# Sheet5.net
KiCad netlist of a schematic drawn in Altium Designer
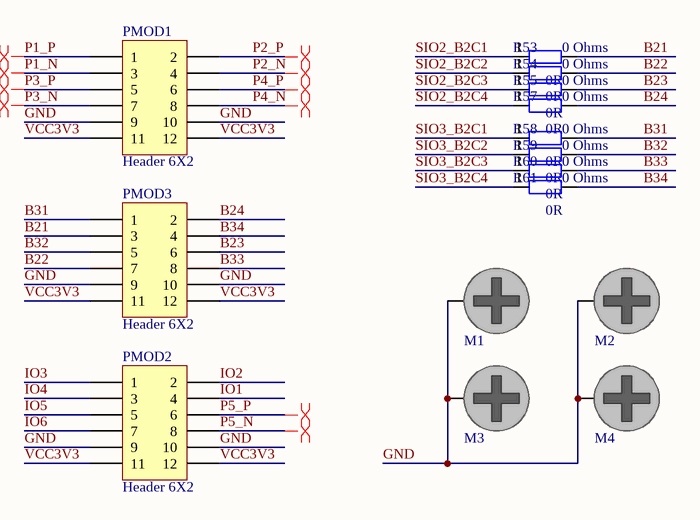
[diagram p0: Sheet5.SchDoc]

(export (version "E")
  (design (tool "Eeschema 10.0.6"))
  (components
    (comp (ref "M1")
      (value "DNP/MH")
      (footprint "SCMH_M2")
      (description "SCREW mouting, M2, 2.0mm diameter and 4.0mm PanHead")
      (libsource (lib "Mechanical") (part "SCMH_M2"))
    )
    (comp (ref "M2")
      (value "DNP/MH")
      (footprint "SCMH_M2")
      (description "SCREW mouting, M2, 2.0mm diameter and 4.0mm PanHead")
      (libsource (lib "Mechanical") (part "SCMH_M2"))
    )
    (comp (ref "M3")
      (value "DNP/MH")
      (footprint "SCMH_M2")
      (description "SCREW mouting, M2, 2.0mm diameter and 4.0mm PanHead")
      (libsource (lib "Mechanical") (part "SCMH_M2"))
    )
    (comp (ref "M4")
      (value "DNP/MH")
      (footprint "SCMH_M2")
      (description "SCREW mouting, M2, 2.0mm diameter and 4.0mm PanHead")
      (libsource (lib "Mechanical") (part "SCMH_M2"))
    )
    (comp (ref "PMOD1")
      (value "Header 6X2")
      (footprint "HDR2X6")
      (description "Header, 6-Pin, Dual row")
      (fields (field (name "PUBLISHER") "Altium Limited"))
      (libsource (lib "Miscellaneous Connectors") (part "Header 6X2"))
    )
    (comp (ref "PMOD2")
      (value "Header 6X2")
      (footprint "HDR2X6")
      (description "Header, 6-Pin, Dual row")
      (fields (field (name "PUBLISHER") "Altium Limited"))
      (libsource (lib "Miscellaneous Connectors") (part "Header 6X2"))
    )
    (comp (ref "PMOD3")
      (value "Header 6X2")
      (footprint "HDR2X6")
      (description "Header, 6-Pin, Dual row")
      (fields (field (name "PUBLISHER") "Altium Limited"))
      (libsource (lib "Miscellaneous Connectors") (part "Header 6X2"))
    )
    (comp (ref "R53")
      (value "0 Ohms")
      (footprint "RES0402i")
      (description "0402, 0R")
      (fields
        (field (name "PART NUMBER") "CRCW04020000Z0EDC")
        (field (name "VOLTAGE") "50V")
        (field (name "ALTIUM_VALUE") "0R")
      )
      (libsource (lib "AmpherLib") (part "Res_0R_0402"))
    )
    (comp (ref "R54")
      (value "0 Ohms")
      (footprint "RES0402i")
      (description "0402, 0R")
      (fields
        (field (name "PART NUMBER") "CRCW04020000Z0EDC")
        (field (name "VOLTAGE") "50V")
        (field (name "ALTIUM_VALUE") "0R")
      )
      (libsource (lib "AmpherLib") (part "Res_0R_0402"))
    )
    (comp (ref "R55")
      (value "0 Ohms")
      (footprint "RES0402i")
      (description "0402, 0R")
      (fields
        (field (name "PART NUMBER") "CRCW04020000Z0EDC")
        (field (name "VOLTAGE") "50V")
        (field (name "ALTIUM_VALUE") "0R")
      )
      (libsource (lib "AmpherLib") (part "Res_0R_0402"))
    )
    (comp (ref "R57")
      (value "0 Ohms")
      (footprint "RES0402i")
      (description "0402, 0R")
      (fields
        (field (name "PART NUMBER") "CRCW04020000Z0EDC")
        (field (name "VOLTAGE") "50V")
        (field (name "ALTIUM_VALUE") "0R")
      )
      (libsource (lib "AmpherLib") (part "Res_0R_0402"))
    )
    (comp (ref "R58")
      (value "0 Ohms")
      (footprint "RES0402i")
      (description "0402, 0R")
      (fields
        (field (name "PART NUMBER") "CRCW04020000Z0EDC")
        (field (name "VOLTAGE") "50V")
        (field (name "ALTIUM_VALUE") "0R")
      )
      (libsource (lib "AmpherLib") (part "Res_0R_0402"))
    )
    (comp (ref "R59")
      (value "0 Ohms")
      (footprint "RES0402i")
      (description "0402, 0R")
      (fields
        (field (name "PART NUMBER") "CRCW04020000Z0EDC")
        (field (name "VOLTAGE") "50V")
        (field (name "ALTIUM_VALUE") "0R")
      )
      (libsource (lib "AmpherLib") (part "Res_0R_0402"))
    )
    (comp (ref "R60")
      (value "0 Ohms")
      (footprint "RES0402i")
      (description "0402, 0R")
      (fields
        (field (name "PART NUMBER") "CRCW04020000Z0EDC")
        (field (name "VOLTAGE") "50V")
        (field (name "ALTIUM_VALUE") "0R")
      )
      (libsource (lib "AmpherLib") (part "Res_0R_0402"))
    )
    (comp (ref "R61")
      (value "0 Ohms")
      (footprint "RES0402i")
      (description "0402, 0R")
      (fields
        (field (name "PART NUMBER") "CRCW04020000Z0EDC")
        (field (name "VOLTAGE") "50V")
        (field (name "ALTIUM_VALUE") "0R")
      )
      (libsource (lib "AmpherLib") (part "Res_0R_0402"))
    )
  )
  (nets
    (net (code "1") (name "/B21") (class "Default")
      (node (ref "PMOD3") (pin "3") (pinfunction "3_3") (pintype "passive"))
      (node (ref "R53") (pin "2") (pinfunction "2_2") (pintype "passive"))
    )
    (net (code "2") (name "/B22") (class "Default")
      (node (ref "PMOD3") (pin "7") (pinfunction "7_7") (pintype "passive"))
      (node (ref "R54") (pin "2") (pinfunction "2_2") (pintype "passive"))
    )
    (net (code "3") (name "/B23") (class "Default")
      (node (ref "PMOD3") (pin "6") (pinfunction "6_6") (pintype "passive"))
      (node (ref "R55") (pin "2") (pinfunction "2_2") (pintype "passive"))
    )
    (net (code "4") (name "/B24") (class "Default")
      (node (ref "PMOD3") (pin "2") (pinfunction "2_2") (pintype "passive"))
      (node (ref "R57") (pin "2") (pinfunction "2_2") (pintype "passive"))
    )
    (net (code "5") (name "/B31") (class "Default")
      (node (ref "PMOD3") (pin "1") (pinfunction "1_1") (pintype "passive"))
      (node (ref "R58") (pin "2") (pinfunction "2_2") (pintype "passive"))
    )
    (net (code "6") (name "/B32") (class "Default")
      (node (ref "PMOD3") (pin "5") (pinfunction "5_5") (pintype "passive"))
      (node (ref "R59") (pin "2") (pinfunction "2_2") (pintype "passive"))
    )
    (net (code "7") (name "/B33") (class "Default")
      (node (ref "PMOD3") (pin "8") (pinfunction "8_8") (pintype "passive"))
      (node (ref "R60") (pin "2") (pinfunction "2_2") (pintype "passive"))
    )
    (net (code "8") (name "/B34") (class "Default")
      (node (ref "PMOD3") (pin "4") (pinfunction "4_4") (pintype "passive"))
      (node (ref "R61") (pin "2") (pinfunction "2_2") (pintype "passive"))
    )
    (net (code "9") (name "/GND") (class "Default")
      (node (ref "M1") (pin "1") (pinfunction "1_1") (pintype "passive"))
      (node (ref "M2") (pin "1") (pinfunction "1_1") (pintype "passive"))
      (node (ref "M3") (pin "1") (pinfunction "1_1") (pintype "passive"))
      (node (ref "M4") (pin "1") (pinfunction "1_1") (pintype "passive"))
      (node (ref "PMOD1") (pin "10") (pinfunction "10_10") (pintype "passive"))
      (node (ref "PMOD1") (pin "9") (pinfunction "9_9") (pintype "passive"))
      (node (ref "PMOD2") (pin "10") (pinfunction "10_10") (pintype "passive"))
      (node (ref "PMOD2") (pin "9") (pinfunction "9_9") (pintype "passive"))
      (node (ref "PMOD3") (pin "10") (pinfunction "10_10") (pintype "passive"))
      (node (ref "PMOD3") (pin "9") (pinfunction "9_9") (pintype "passive"))
    )
    (net (code "10") (name "/IO1") (class "Default")
      (node (ref "PMOD2") (pin "4") (pinfunction "4_4") (pintype "passive"))
    )
    (net (code "11") (name "/IO2") (class "Default")
      (node (ref "PMOD2") (pin "2") (pinfunction "2_2") (pintype "passive"))
    )
    (net (code "12") (name "/IO3") (class "Default")
      (node (ref "PMOD2") (pin "1") (pinfunction "1_1") (pintype "passive"))
    )
    (net (code "13") (name "/IO4") (class "Default")
      (node (ref "PMOD2") (pin "3") (pinfunction "3_3") (pintype "passive"))
    )
    (net (code "14") (name "/IO5") (class "Default")
      (node (ref "PMOD2") (pin "5") (pinfunction "5_5") (pintype "passive"))
    )
    (net (code "15") (name "/IO6") (class "Default")
      (node (ref "PMOD2") (pin "7") (pinfunction "7_7") (pintype "passive"))
    )
    (net (code "16") (name "/P1_N") (class "Default")
      (node (ref "PMOD1") (pin "3") (pinfunction "3_3") (pintype "passive"))
    )
    (net (code "17") (name "/P1_P") (class "Default")
      (node (ref "PMOD1") (pin "1") (pinfunction "1_1") (pintype "passive"))
    )
    (net (code "18") (name "/P2_N") (class "Default")
      (node (ref "PMOD1") (pin "4") (pinfunction "4_4") (pintype "passive"))
    )
    (net (code "19") (name "/P2_P") (class "Default")
      (node (ref "PMOD1") (pin "2") (pinfunction "2_2") (pintype "passive"))
    )
    (net (code "20") (name "/P3_N") (class "Default")
      (node (ref "PMOD1") (pin "7") (pinfunction "7_7") (pintype "passive"))
    )
    (net (code "21") (name "/P3_P") (class "Default")
      (node (ref "PMOD1") (pin "5") (pinfunction "5_5") (pintype "passive"))
    )
    (net (code "22") (name "/P4_N") (class "Default")
      (node (ref "PMOD1") (pin "8") (pinfunction "8_8") (pintype "passive"))
    )
    (net (code "23") (name "/P4_P") (class "Default")
      (node (ref "PMOD1") (pin "6") (pinfunction "6_6") (pintype "passive"))
    )
    (net (code "24") (name "/P5_N") (class "Default")
      (node (ref "PMOD2") (pin "8") (pinfunction "8_8") (pintype "passive"))
    )
    (net (code "25") (name "/P5_P") (class "Default")
      (node (ref "PMOD2") (pin "6") (pinfunction "6_6") (pintype "passive"))
    )
    (net (code "26") (name "/SIO2_B2C1") (class "Default")
      (node (ref "R53") (pin "1") (pinfunction "1_1") (pintype "passive"))
    )
    (net (code "27") (name "/SIO2_B2C2") (class "Default")
      (node (ref "R54") (pin "1") (pinfunction "1_1") (pintype "passive"))
    )
    (net (code "28") (name "/SIO2_B2C3") (class "Default")
      (node (ref "R55") (pin "1") (pinfunction "1_1") (pintype "passive"))
    )
    (net (code "29") (name "/SIO2_B2C4") (class "Default")
      (node (ref "R57") (pin "1") (pinfunction "1_1") (pintype "passive"))
    )
    (net (code "30") (name "/SIO3_B2C1") (class "Default")
      (node (ref "R58") (pin "1") (pinfunction "1_1") (pintype "passive"))
    )
    (net (code "31") (name "/SIO3_B2C2") (class "Default")
      (node (ref "R59") (pin "1") (pinfunction "1_1") (pintype "passive"))
    )
    (net (code "32") (name "/SIO3_B2C3") (class "Default")
      (node (ref "R60") (pin "1") (pinfunction "1_1") (pintype "passive"))
    )
    (net (code "33") (name "/SIO3_B2C4") (class "Default")
      (node (ref "R61") (pin "1") (pinfunction "1_1") (pintype "passive"))
    )
    (net (code "34") (name "/VCC3V3") (class "Default")
      (node (ref "PMOD1") (pin "11") (pinfunction "11_11") (pintype "passive"))
      (node (ref "PMOD1") (pin "12") (pinfunction "12_12") (pintype "passive"))
      (node (ref "PMOD2") (pin "11") (pinfunction "11_11") (pintype "passive"))
      (node (ref "PMOD2") (pin "12") (pinfunction "12_12") (pintype "passive"))
      (node (ref "PMOD3") (pin "11") (pinfunction "11_11") (pintype "passive"))
      (node (ref "PMOD3") (pin "12") (pinfunction "12_12") (pintype "passive"))
    )
  )
)
